# A-__LCP037BK32ET8-48V-SCH-V1_2-20230321.net
KiCad netlist of a schematic drawn in Altium Designer
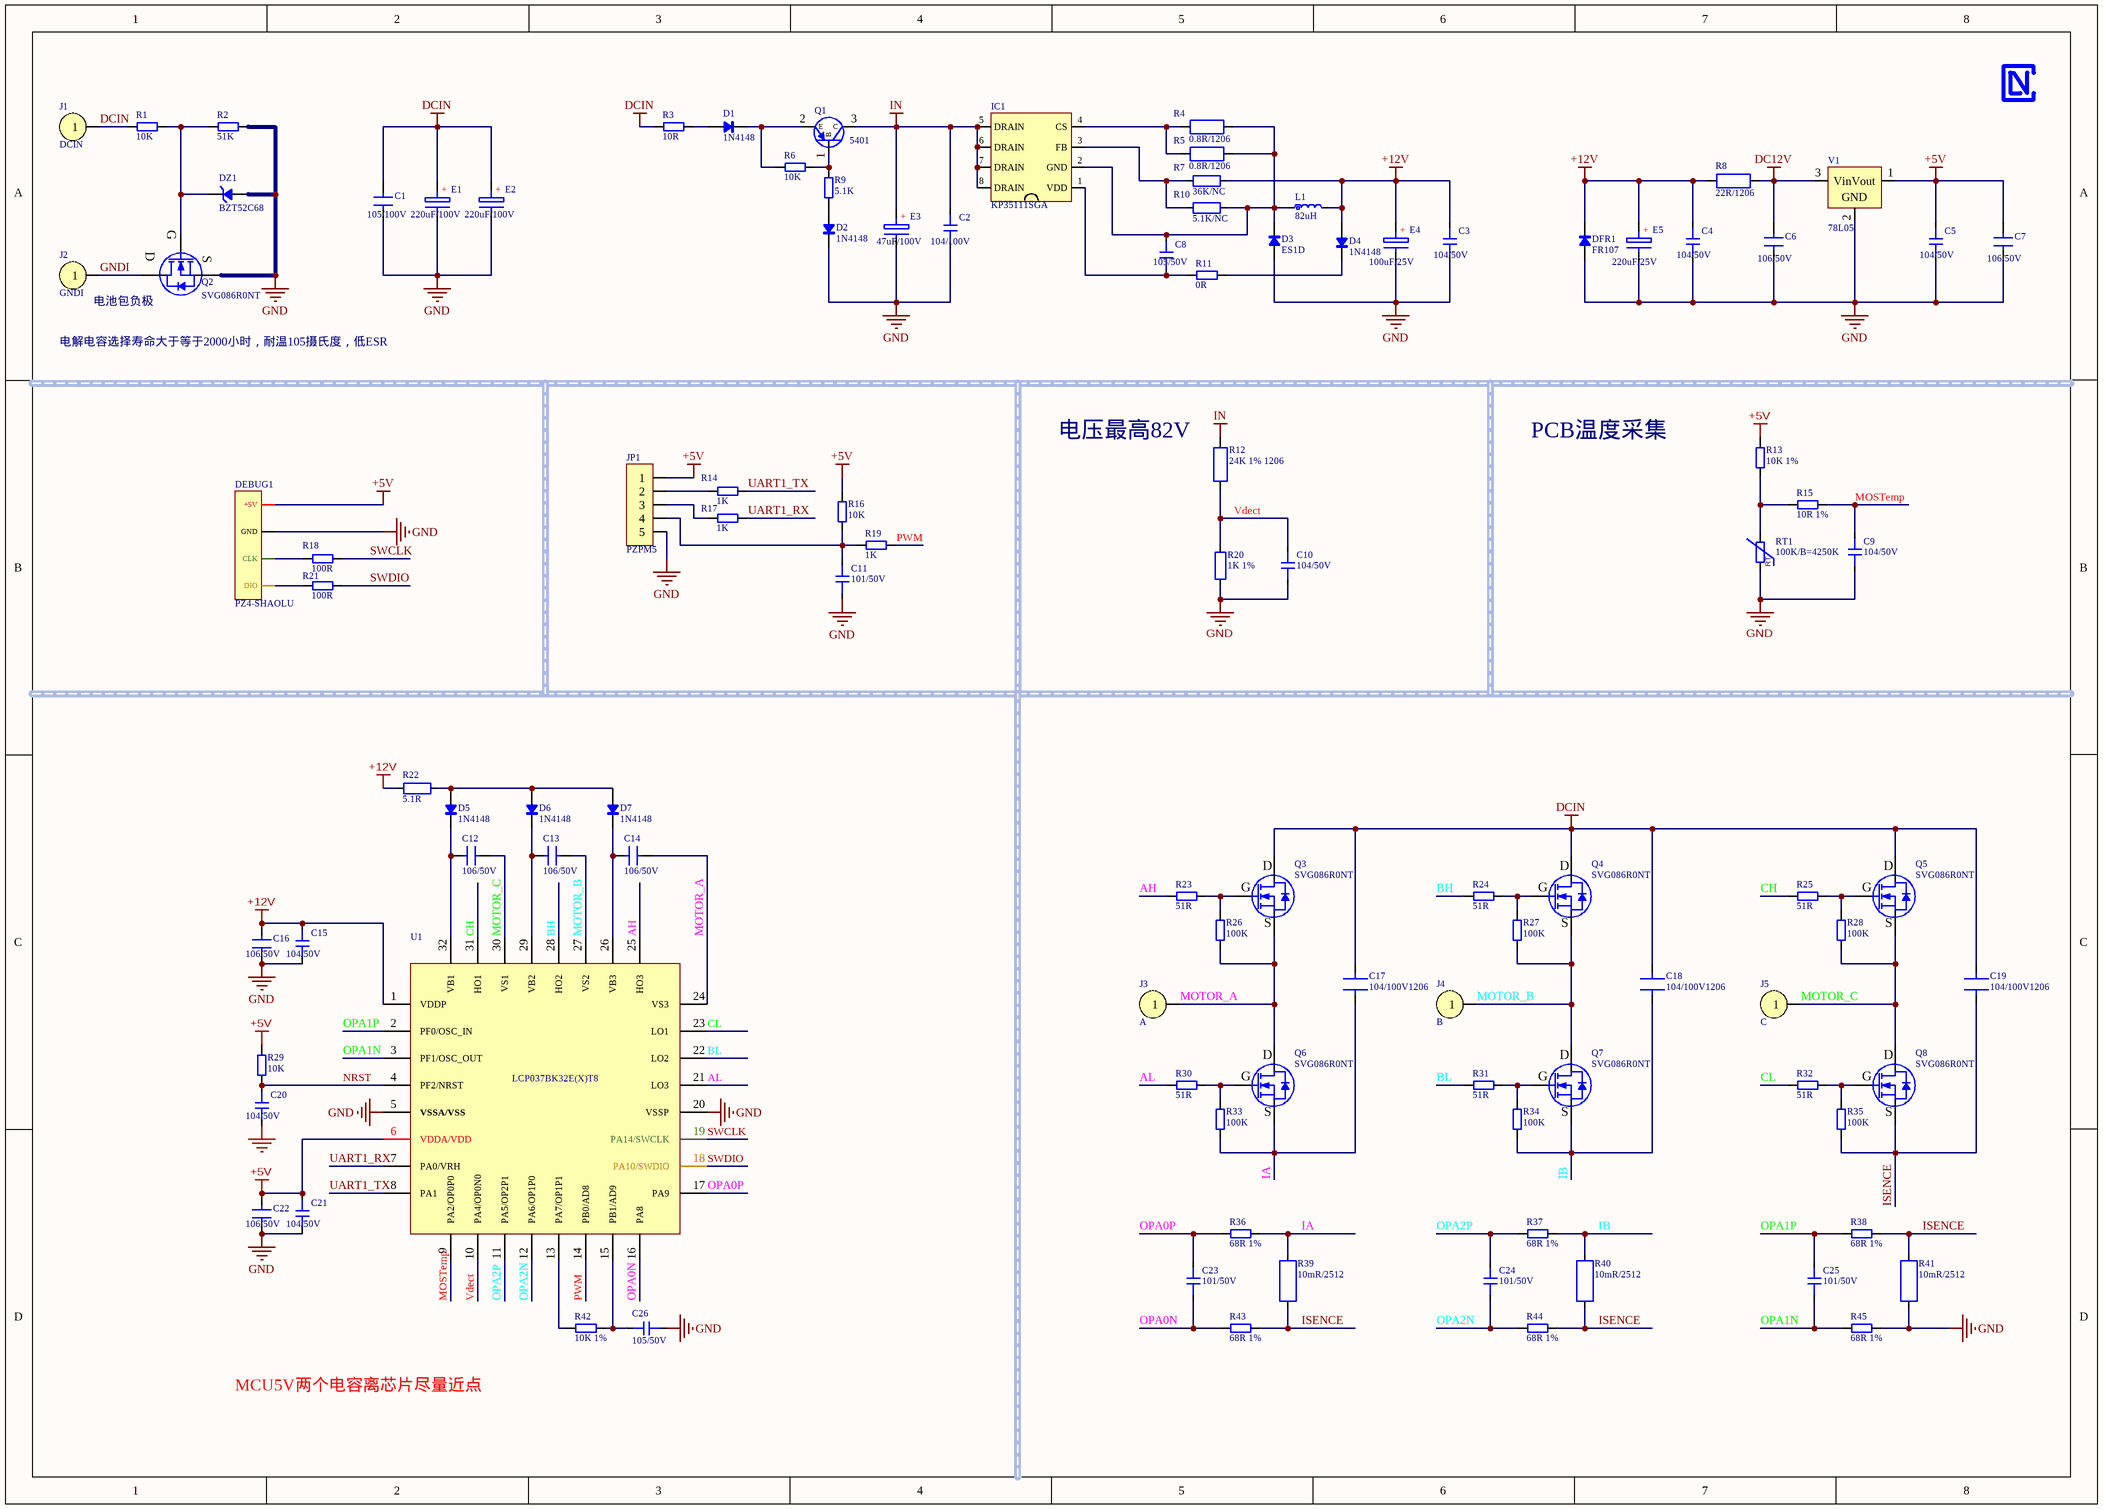
[diagram p0: A-水泵_LCP037BK32ET8-48V-SCH-V1.2-20230321.SchDoc]

(export (version "E")
  (design (tool "Eeschema 10.0.6"))
  (components
    (comp (ref "C1")
      (value "105/100V")
      (footprint "C0805")
      (description "0805")
      (libsource (lib "LNCHIP-KU-V1.2-20230210") (part "A_CAP_8"))
    )
    (comp (ref "C2")
      (value "104/100V")
      (footprint "C0603")
      (description "0603")
      (libsource (lib "LNCHIP-KU-V1.2-20230210") (part "A_CAP_6"))
    )
    (comp (ref "C3")
      (value "104/50V")
      (footprint "C0603")
      (description "0603")
      (libsource (lib "LNCHIP-KU-V1.2-20230210") (part "A_CAP_6"))
    )
    (comp (ref "C4")
      (value "104/50V")
      (footprint "C0603")
      (description "0603")
      (libsource (lib "LNCHIP-KU-V1.2-20230210") (part "A_CAP_6"))
    )
    (comp (ref "C5")
      (value "104/50V")
      (footprint "C0603")
      (description "0603")
      (libsource (lib "LNCHIP-KU-V1.2-20230210") (part "A_CAP_6"))
    )
    (comp (ref "C6")
      (value "106/50V")
      (footprint "C0805")
      (description "0805")
      (libsource (lib "LNCHIP-KU-V1.2-20230210") (part "A_CAP_8"))
    )
    (comp (ref "C7")
      (value "106/50V")
      (footprint "C0805")
      (description "0805")
      (libsource (lib "LNCHIP-KU-V1.2-20230210") (part "A_CAP_8"))
    )
    (comp (ref "C8")
      (value "105/50V")
      (footprint "C0603")
      (description "0603")
      (libsource (lib "LNCHIP-KU-V1.2-20230210") (part "A_CAP_6"))
    )
    (comp (ref "C9")
      (value "104/50V")
      (footprint "C0603")
      (description "0603")
      (libsource (lib "LNCHIP-KU-V1.2-20230210") (part "A_CAP_6"))
    )
    (comp (ref "C10")
      (value "104/50V")
      (footprint "C0603")
      (description "0603")
      (libsource (lib "LNCHIP-KU-V1.2-20230210") (part "A_CAP_6"))
    )
    (comp (ref "C11")
      (value "101/50V")
      (footprint "C0603")
      (description "0603")
      (libsource (lib "LNCHIP-KU-V1.2-20230210") (part "A_CAP_6"))
    )
    (comp (ref "C12")
      (value "106/50V")
      (footprint "C0805")
      (description "0805")
      (libsource (lib "LNCHIP-KU-V1.2-20230210") (part "A_CAP_8"))
    )
    (comp (ref "C13")
      (value "106/50V")
      (footprint "C0805")
      (description "0805")
      (libsource (lib "LNCHIP-KU-V1.2-20230210") (part "A_CAP_8"))
    )
    (comp (ref "C14")
      (value "106/50V")
      (footprint "C0805")
      (description "0805")
      (libsource (lib "LNCHIP-KU-V1.2-20230210") (part "A_CAP_8"))
    )
    (comp (ref "C15")
      (value "104/50V")
      (footprint "C0603")
      (description "0603")
      (libsource (lib "LNCHIP-KU-V1.2-20230210") (part "A_CAP_6"))
    )
    (comp (ref "C16")
      (value "106/50V")
      (footprint "C0805")
      (description "0805")
      (libsource (lib "LNCHIP-KU-V1.2-20230210") (part "A_CAP_8"))
    )
    (comp (ref "C17")
      (value "104/100V1206")
      (footprint "C1206")
      (description "1206/1808")
      (libsource (lib "LNCHIP-KU-V1.2-20230210") (part "A_CAP_12"))
    )
    (comp (ref "C18")
      (value "104/100V1206")
      (footprint "C1206")
      (description "1206/1808")
      (libsource (lib "LNCHIP-KU-V1.2-20230210") (part "A_CAP_12"))
    )
    (comp (ref "C19")
      (value "104/100V1206")
      (footprint "C1206")
      (description "1206/1808")
      (libsource (lib "LNCHIP-KU-V1.2-20230210") (part "A_CAP_12"))
    )
    (comp (ref "C20")
      (value "104/50V")
      (footprint "C0603")
      (description "0603")
      (libsource (lib "LNCHIP-KU-V1.2-20230210") (part "A_CAP_6"))
    )
    (comp (ref "C21")
      (value "104/50V")
      (footprint "C0603")
      (description "0603")
      (libsource (lib "LNCHIP-KU-V1.2-20230210") (part "A_CAP_6"))
    )
    (comp (ref "C22")
      (value "106/50V")
      (footprint "C0805")
      (description "0805")
      (libsource (lib "LNCHIP-KU-V1.2-20230210") (part "A_CAP_8"))
    )
    (comp (ref "C23")
      (value "101/50V")
      (footprint "C0603")
      (description "0603")
      (libsource (lib "LNCHIP-KU-V1.2-20230210") (part "A_CAP_6"))
    )
    (comp (ref "C24")
      (value "101/50V")
      (footprint "C0603")
      (description "0603")
      (libsource (lib "LNCHIP-KU-V1.2-20230210") (part "A_CAP_6"))
    )
    (comp (ref "C25")
      (value "101/50V")
      (footprint "C0603")
      (description "0603")
      (libsource (lib "LNCHIP-KU-V1.2-20230210") (part "A_CAP_6"))
    )
    (comp (ref "C26")
      (value "105/50V")
      (footprint "C0603")
      (description "0603")
      (libsource (lib "LNCHIP-KU-V1.2-20230210") (part "A_CAP_6"))
    )
    (comp (ref "D1")
      (value "1N4148")
      (footprint "SOD-123")
      (description "二极管/高效率/通用")
      (libsource (lib "LNCHIP-KU-V1.2-20230210") (part "DIO"))
    )
    (comp (ref "D2")
      (value "1N4148")
      (footprint "SOD-123")
      (description "二极管/高效率/通用")
      (libsource (lib "LNCHIP-KU-V1.2-20230210") (part "DIO"))
    )
    (comp (ref "D3")
      (value "ES1D")
      (footprint "SOD-123")
      (description "二极管/高效率/通用")
      (libsource (lib "LNCHIP-KU-V1.2-20230210") (part "DIO"))
    )
    (comp (ref "D4")
      (value "1N4148")
      (footprint "SOD-123")
      (description "二极管/高效率/通用")
      (libsource (lib "LNCHIP-KU-V1.2-20230210") (part "DIO"))
    )
    (comp (ref "D5")
      (value "1N4148")
      (footprint "SOD-123")
      (description "二极管/高效率/通用")
      (libsource (lib "LNCHIP-KU-V1.2-20230210") (part "DIO"))
    )
    (comp (ref "D6")
      (value "1N4148")
      (footprint "SOD-123")
      (description "二极管/高效率/通用")
      (libsource (lib "LNCHIP-KU-V1.2-20230210") (part "DIO"))
    )
    (comp (ref "D7")
      (value "1N4148")
      (footprint "SOD-123")
      (description "二极管/高效率/通用")
      (libsource (lib "LNCHIP-KU-V1.2-20230210") (part "DIO"))
    )
    (comp (ref "DEBUG1")
      (value "PZ4-SHAOLU")
      (footprint "PZ2.54-D-4P")
      (description "烧录口")
      (libsource (lib "LNCHIP-KU-V1.2-20230210") (part "PZ4-SHAOLU"))
    )
    (comp (ref "DFR1")
      (value "FR107")
      (footprint "SMA")
      (description "快/超快恢复二极管")
      (libsource (lib "LNCHIP-KU-V1.2-20230210") (part "DIO_FR(E)D"))
    )
    (comp (ref "DZ1")
      (value "BZT52C68")
      (footprint "SOD-123")
      (description "稳压管")
      (libsource (lib "LNCHIP-KU-V1.2-20230210") (part "DIO_ZENER"))
    )
    (comp (ref "E1")
      (value "220uF/100V")
      (footprint "CE-5.0-10")
      (description "直插电解电容")
      (libsource (lib "LNCHIP-KU-V1.2-20230210") (part "A_CAP_CE_DIP"))
    )
    (comp (ref "E2")
      (value "220uF/100V")
      (footprint "CE-5.0-10")
      (description "直插电解电容")
      (libsource (lib "LNCHIP-KU-V1.2-20230210") (part "A_CAP_CE_DIP"))
    )
    (comp (ref "E3")
      (value "47uF/100V")
      (footprint "CE-3.5-8")
      (description "直插电解电容")
      (libsource (lib "LNCHIP-KU-V1.2-20230210") (part "A_CAP_CE_DIP"))
    )
    (comp (ref "E4")
      (value "100uF/25V")
      (footprint "CE-2.5-5")
      (description "直插电解电容")
      (libsource (lib "LNCHIP-KU-V1.2-20230210") (part "A_CAP_CE_DIP"))
    )
    (comp (ref "E5")
      (value "220uF/25V")
      (footprint "CE-2.5-5")
      (description "直插电解电容")
      (libsource (lib "LNCHIP-KU-V1.2-20230210") (part "A_CAP_CE_DIP"))
    )
    (comp (ref "IC1")
      (value "KP35111SGA")
      (footprint "SOP-8_150_50")
      (description "功率电子开关/BUCK_DC-DC")
      (libsource (lib "LNCHIP-KU-V1.2-20230210") (part "IC_DY_KP35111"))
    )
    (comp (ref "J1")
      (value "DCIN")
      (footprint "HOLD-16AWG")
      (description "直插孔")
      (libsource (lib "LNCHIP-KU-V1.2-20230210") (part "CON_DIP"))
    )
    (comp (ref "J2")
      (value "GNDI")
      (footprint "HOLD-16AWG")
      (description "直插孔")
      (libsource (lib "LNCHIP-KU-V1.2-20230210") (part "CON_DIP"))
    )
    (comp (ref "J3")
      (value "A")
      (footprint "HOLD-16AWG")
      (description "直插孔")
      (libsource (lib "LNCHIP-KU-V1.2-20230210") (part "CON_DIP"))
    )
    (comp (ref "J4")
      (value "B")
      (footprint "HOLD-16AWG")
      (description "直插孔")
      (libsource (lib "LNCHIP-KU-V1.2-20230210") (part "CON_DIP"))
    )
    (comp (ref "J5")
      (value "C")
      (footprint "HOLD-16AWG")
      (description "直插孔")
      (libsource (lib "LNCHIP-KU-V1.2-20230210") (part "CON_DIP"))
    )
    (comp (ref "JP1")
      (value "PZPM5")
      (footprint "PZ2.54-D-5P")
      (description "排针排母")
      (libsource (lib "LNCHIP-KU-V1.2-20230210") (part "PZPM5"))
    )
    (comp (ref "L1")
      (value "82uH")
      (footprint "L-CDRH74")
      (description "贴片电感")
      (libsource (lib "LNCHIP-KU-V1.2-20230210") (part "INDUCTOR"))
    )
    (comp (ref "Q1")
      (value "5401")
      (footprint "SOT23-3")
      (description "PNP三极管")
      (libsource (lib "LNCHIP-KU-V1.2-20230210") (part "D_BJT_N"))
    )
    (comp (ref "Q2")
      (value "SVG086R0NT")
      (footprint "TO220")
      (description "N沟道")
      (libsource (lib "LNCHIP-KU-V1.2-20230210") (part "D_MOS_N-2D/"))
    )
    (comp (ref "Q3")
      (value "SVG086R0NT")
      (footprint "TO220")
      (description "N沟道")
      (libsource (lib "LNCHIP-KU-V1.2-20230210") (part "D_MOS_N-2D/"))
    )
    (comp (ref "Q4")
      (value "SVG086R0NT")
      (footprint "TO220")
      (description "N沟道")
      (libsource (lib "LNCHIP-KU-V1.2-20230210") (part "D_MOS_N-2D/"))
    )
    (comp (ref "Q5")
      (value "SVG086R0NT")
      (footprint "TO220")
      (description "N沟道")
      (libsource (lib "LNCHIP-KU-V1.2-20230210") (part "D_MOS_N-2D/"))
    )
    (comp (ref "Q6")
      (value "SVG086R0NT")
      (footprint "TO220")
      (description "N沟道")
      (libsource (lib "LNCHIP-KU-V1.2-20230210") (part "D_MOS_N-2D/"))
    )
    (comp (ref "Q7")
      (value "SVG086R0NT")
      (footprint "TO220")
      (description "N沟道")
      (libsource (lib "LNCHIP-KU-V1.2-20230210") (part "D_MOS_N-2D/"))
    )
    (comp (ref "Q8")
      (value "SVG086R0NT")
      (footprint "TO220")
      (description "N沟道")
      (libsource (lib "LNCHIP-KU-V1.2-20230210") (part "D_MOS_N-2D/"))
    )
    (comp (ref "R1")
      (value "10K")
      (footprint "R0603")
      (description "0603")
      (libsource (lib "LNCHIP-KU-V1.2-20230210") (part "A_RES_6"))
    )
    (comp (ref "R2")
      (value "51K")
      (footprint "R0603")
      (description "0603")
      (libsource (lib "LNCHIP-KU-V1.2-20230210") (part "A_RES_6"))
    )
    (comp (ref "R3")
      (value "10R")
      (footprint "R0603")
      (description "0603")
      (libsource (lib "LNCHIP-KU-V1.2-20230210") (part "A_RES_6"))
    )
    (comp (ref "R4")
      (value "0.8R/1206")
      (footprint "R1206")
      (description "1206")
      (libsource (lib "LNCHIP-KU-V1.2-20230210") (part "A_RES_12"))
    )
    (comp (ref "R5")
      (value "0.8R/1206")
      (footprint "R1206")
      (description "1206")
      (libsource (lib "LNCHIP-KU-V1.2-20230210") (part "A_RES_12"))
    )
    (comp (ref "R6")
      (value "10K")
      (footprint "R0603")
      (description "0603")
      (libsource (lib "LNCHIP-KU-V1.2-20230210") (part "A_RES_6"))
    )
    (comp (ref "R7")
      (value "36K/NC")
      (footprint "R0805")
      (description "0805")
      (libsource (lib "LNCHIP-KU-V1.2-20230210") (part "A_RES_8"))
    )
    (comp (ref "R8")
      (value "22R/1206")
      (footprint "R1206")
      (description "1206")
      (libsource (lib "LNCHIP-KU-V1.2-20230210") (part "A_RES_12"))
    )
    (comp (ref "R9")
      (value "5.1K")
      (footprint "R0603")
      (description "0603")
      (libsource (lib "LNCHIP-KU-V1.2-20230210") (part "A_RES_6"))
    )
    (comp (ref "R10")
      (value "5.1K/NC")
      (footprint "R0805")
      (description "0805")
      (libsource (lib "LNCHIP-KU-V1.2-20230210") (part "A_RES_8"))
    )
    (comp (ref "R11")
      (value "0R")
      (footprint "R0603")
      (description "0603")
      (libsource (lib "LNCHIP-KU-V1.2-20230210") (part "A_RES_6"))
    )
    (comp (ref "R12")
      (value "24K 1% 1206")
      (footprint "R1206")
      (description "1206")
      (libsource (lib "LNCHIP-KU-V1.2-20230210") (part "A_RES_12"))
    )
    (comp (ref "R13")
      (value "10K 1%")
      (footprint "R0603")
      (description "0603")
      (libsource (lib "LNCHIP-KU-V1.2-20230210") (part "A_RES_6"))
    )
    (comp (ref "R14")
      (value "1K")
      (footprint "R0603")
      (description "0603")
      (libsource (lib "LNCHIP-KU-V1.2-20230210") (part "A_RES_6"))
    )
    (comp (ref "R15")
      (value "10R 1%")
      (footprint "R0603")
      (description "0603")
      (libsource (lib "LNCHIP-KU-V1.2-20230210") (part "A_RES_6"))
    )
    (comp (ref "R16")
      (value "10K")
      (footprint "R0603")
      (description "0603")
      (libsource (lib "LNCHIP-KU-V1.2-20230210") (part "A_RES_6"))
    )
    (comp (ref "R17")
      (value "1K")
      (footprint "R0603")
      (description "0603")
      (libsource (lib "LNCHIP-KU-V1.2-20230210") (part "A_RES_6"))
    )
    (comp (ref "R18")
      (value "100R")
      (footprint "R0603")
      (description "0603")
      (libsource (lib "LNCHIP-KU-V1.2-20230210") (part "A_RES_6"))
    )
    (comp (ref "R19")
      (value "1K")
      (footprint "R0603")
      (description "0603")
      (libsource (lib "LNCHIP-KU-V1.2-20230210") (part "A_RES_6"))
    )
    (comp (ref "R20")
      (value "1K 1%")
      (footprint "R0805")
      (description "0805")
      (libsource (lib "LNCHIP-KU-V1.2-20230210") (part "A_RES_8"))
    )
    (comp (ref "R21")
      (value "100R")
      (footprint "R0603")
      (description "0603")
      (libsource (lib "LNCHIP-KU-V1.2-20230210") (part "A_RES_6"))
    )
    (comp (ref "R22")
      (value "5.1R")
      (footprint "R0805")
      (description "0805")
      (libsource (lib "LNCHIP-KU-V1.2-20230210") (part "A_RES_8"))
    )
    (comp (ref "R23")
      (value "51R")
      (footprint "R0603")
      (description "0603")
      (libsource (lib "LNCHIP-KU-V1.2-20230210") (part "A_RES_6"))
    )
    (comp (ref "R24")
      (value "51R")
      (footprint "R0603")
      (description "0603")
      (libsource (lib "LNCHIP-KU-V1.2-20230210") (part "A_RES_6"))
    )
    (comp (ref "R25")
      (value "51R")
      (footprint "R0603")
      (description "0603")
      (libsource (lib "LNCHIP-KU-V1.2-20230210") (part "A_RES_6"))
    )
    (comp (ref "R26")
      (value "100K")
      (footprint "R0603")
      (description "0603")
      (libsource (lib "LNCHIP-KU-V1.2-20230210") (part "A_RES_6"))
    )
    (comp (ref "R27")
      (value "100K")
      (footprint "R0603")
      (description "0603")
      (libsource (lib "LNCHIP-KU-V1.2-20230210") (part "A_RES_6"))
    )
    (comp (ref "R28")
      (value "100K")
      (footprint "R0603")
      (description "0603")
      (libsource (lib "LNCHIP-KU-V1.2-20230210") (part "A_RES_6"))
    )
    (comp (ref "R29")
      (value "10K")
      (footprint "R0603")
      (description "0603")
      (libsource (lib "LNCHIP-KU-V1.2-20230210") (part "A_RES_6"))
    )
    (comp (ref "R30")
      (value "51R")
      (footprint "R0603")
      (description "0603")
      (libsource (lib "LNCHIP-KU-V1.2-20230210") (part "A_RES_6"))
    )
    (comp (ref "R31")
      (value "51R")
      (footprint "R0603")
      (description "0603")
      (libsource (lib "LNCHIP-KU-V1.2-20230210") (part "A_RES_6"))
    )
    (comp (ref "R32")
      (value "51R")
      (footprint "R0603")
      (description "0603")
      (libsource (lib "LNCHIP-KU-V1.2-20230210") (part "A_RES_6"))
    )
    (comp (ref "R33")
      (value "100K")
      (footprint "R0603")
      (description "0603")
      (libsource (lib "LNCHIP-KU-V1.2-20230210") (part "A_RES_6"))
    )
    (comp (ref "R34")
      (value "100K")
      (footprint "R0603")
      (description "0603")
      (libsource (lib "LNCHIP-KU-V1.2-20230210") (part "A_RES_6"))
    )
    (comp (ref "R35")
      (value "100K")
      (footprint "R0603")
      (description "0603")
      (libsource (lib "LNCHIP-KU-V1.2-20230210") (part "A_RES_6"))
    )
    (comp (ref "R36")
      (value "68R 1%")
      (footprint "R0603")
      (description "0603")
      (libsource (lib "LNCHIP-KU-V1.2-20230210") (part "A_RES_6"))
    )
    (comp (ref "R37")
      (value "68R 1%")
      (footprint "R0603")
      (description "0603")
      (libsource (lib "LNCHIP-KU-V1.2-20230210") (part "A_RES_6"))
    )
    (comp (ref "R38")
      (value "68R 1%")
      (footprint "R0603")
      (description "0603")
      (libsource (lib "LNCHIP-KU-V1.2-20230210") (part "A_RES_6"))
    )
    (comp (ref "R39")
      (value "10mR/2512")
      (footprint "R2512")
      (description "2512")
      (libsource (lib "LNCHIP-KU-V1.2-20230210") (part "A_RES_25"))
    )
    (comp (ref "R40")
      (value "10mR/2512")
      (footprint "R2512")
      (description "2512")
      (libsource (lib "LNCHIP-KU-V1.2-20230210") (part "A_RES_25"))
    )
    (comp (ref "R41")
      (value "10mR/2512")
      (footprint "R2512")
      (description "2512")
      (libsource (lib "LNCHIP-KU-V1.2-20230210") (part "A_RES_25"))
    )
    (comp (ref "R42")
      (value "10K 1%")
      (footprint "R0603")
      (description "0603")
      (libsource (lib "LNCHIP-KU-V1.2-20230210") (part "A_RES_6"))
    )
    (comp (ref "R43")
      (value "68R 1%")
      (footprint "R0603")
      (description "0603")
      (libsource (lib "LNCHIP-KU-V1.2-20230210") (part "A_RES_6"))
    )
    (comp (ref "R44")
      (value "68R 1%")
      (footprint "R0603")
      (description "0603")
      (libsource (lib "LNCHIP-KU-V1.2-20230210") (part "A_RES_6"))
    )
    (comp (ref "R45")
      (value "68R 1%")
      (footprint "R0603")
      (description "0603")
      (libsource (lib "LNCHIP-KU-V1.2-20230210") (part "A_RES_6"))
    )
    (comp (ref "RT1")
      (value "100K/B=4250K")
      (footprint "NTC-S-0603")
      (description "热敏电阻")
      (libsource (lib "LNCHIP-KU-V1.2-20230210") (part "A_RES_NTC_SMD"))
    )
    (comp (ref "U1")
      (value "LCP037BK32E(X)T8")
      (footprint "LNCP-LQFP32-7X7-0.8")
      (description "037合封BK32E(X)T8")
      (libsource (lib "LNCHIP-KU-V1.2-20230210") (part "MCU_电机_32位_037_B1"))
    )
    (comp (ref "V1")
      (value "78L05")
      (footprint "SOT89")
      (description "BUCK_DC-DC")
      (libsource (lib "LNCHIP-KU-V1.2-20230210") (part "LDO_2D/"))
    )
  )
  (nets
    (net (code "1") (name "+5V") (class "Default")
      (node (ref "C21") (pin "1") (pinfunction "1_1") (pintype "passive"))
      (node (ref "C22") (pin "1") (pinfunction "1_1") (pintype "passive"))
      (node (ref "C5") (pin "1") (pinfunction "1_1") (pintype "passive"))
      (node (ref "C7") (pin "1") (pinfunction "1_1") (pintype "passive"))
      (node (ref "DEBUG1") (pin "1") (pinfunction "+5V_1") (pintype "passive"))
      (node (ref "JP1") (pin "1") (pinfunction "1_1") (pintype "passive"))
      (node (ref "R13") (pin "2") (pinfunction "2_2") (pintype "passive"))
      (node (ref "R16") (pin "2") (pinfunction "2_2") (pintype "passive"))
      (node (ref "R29") (pin "2") (pinfunction "2_2") (pintype "passive"))
      (node (ref "U1") (pin "6") (pinfunction "VDDA/VDD_6") (pintype "passive"))
      (node (ref "V1") (pin "1") (pinfunction "Vout_1") (pintype "passive"))
    )
    (net (code "2") (name "+12V") (class "Default")
      (node (ref "C15") (pin "1") (pinfunction "1_1") (pintype "passive"))
      (node (ref "C16") (pin "1") (pinfunction "1_1") (pintype "passive"))
      (node (ref "C3") (pin "1") (pinfunction "1_1") (pintype "passive"))
      (node (ref "C4") (pin "1") (pinfunction "1_1") (pintype "passive"))
      (node (ref "D4") (pin "1") (pinfunction "A_1") (pintype "passive"))
      (node (ref "DFR1") (pin "2") (pinfunction "K_2") (pintype "passive"))
      (node (ref "E4") (pin "1") (pinfunction "1_1") (pintype "passive"))
      (node (ref "E5") (pin "1") (pinfunction "1_1") (pintype "passive"))
      (node (ref "L1") (pin "2") (pinfunction "2_2") (pintype "passive"))
      (node (ref "R22") (pin "1") (pinfunction "1_1") (pintype "passive"))
      (node (ref "R7") (pin "2") (pinfunction "2_2") (pintype "passive"))
      (node (ref "R8") (pin "1") (pinfunction "1_1") (pintype "passive"))
      (node (ref "U1") (pin "1") (pinfunction "VDDP_1") (pintype "passive"))
    )
    (net (code "3") (name "/AH") (class "Default")
      (node (ref "R23") (pin "1") (pinfunction "1_1") (pintype "passive"))
      (node (ref "U1") (pin "25") (pinfunction "HO3_25") (pintype "passive"))
    )
    (net (code "4") (name "/AL") (class "Default")
      (node (ref "R30") (pin "1") (pinfunction "1_1") (pintype "passive"))
      (node (ref "U1") (pin "21") (pinfunction "LO3_21") (pintype "passive"))
    )
    (net (code "5") (name "/BH") (class "Default")
      (node (ref "R24") (pin "1") (pinfunction "1_1") (pintype "passive"))
      (node (ref "U1") (pin "28") (pinfunction "HO2_28") (pintype "passive"))
    )
    (net (code "6") (name "/BL") (class "Default")
      (node (ref "R31") (pin "1") (pinfunction "1_1") (pintype "passive"))
      (node (ref "U1") (pin "22") (pinfunction "LO2_22") (pintype "passive"))
    )
    (net (code "7") (name "/CH") (class "Default")
      (node (ref "R25") (pin "1") (pinfunction "1_1") (pintype "passive"))
      (node (ref "U1") (pin "31") (pinfunction "HO1_31") (pintype "passive"))
    )
    (net (code "8") (name "/CL") (class "Default")
      (node (ref "R32") (pin "1") (pinfunction "1_1") (pintype "passive"))
      (node (ref "U1") (pin "23") (pinfunction "LO1_23") (pintype "passive"))
    )
    (net (code "9") (name "/GNDI") (class "Default")
      (node (ref "J2") (pin "1") (pinfunction "1_1") (pintype "passive"))
      (node (ref "Q2") (pin "2") (pinfunction "D_2") (pintype "passive"))
    )
    (net (code "10") (name "/IA") (class "Default")
      (node (ref "C17") (pin "2") (pinfunction "2_2") (pintype "passive"))
      (node (ref "Q6") (pin "3") (pinfunction "S_3") (pintype "passive"))
      (node (ref "R33") (pin "1") (pinfunction "1_1") (pintype "passive"))
      (node (ref "R36") (pin "2") (pinfunction "2_2") (pintype "passive"))
      (node (ref "R39") (pin "2") (pinfunction "2_2") (pintype "passive"))
    )
    (net (code "11") (name "/IB") (class "Default")
      (node (ref "C18") (pin "2") (pinfunction "2_2") (pintype "passive"))
      (node (ref "Q7") (pin "3") (pinfunction "S_3") (pintype "passive"))
      (node (ref "R34") (pin "1") (pinfunction "1_1") (pintype "passive"))
      (node (ref "R37") (pin "2") (pinfunction "2_2") (pintype "passive"))
      (node (ref "R40") (pin "2") (pinfunction "2_2") (pintype "passive"))
    )
    (net (code "12") (name "/ISENCE") (class "Default")
      (node (ref "C19") (pin "2") (pinfunction "2_2") (pintype "passive"))
      (node (ref "Q8") (pin "3") (pinfunction "S_3") (pintype "passive"))
      (node (ref "R35") (pin "1") (pinfunction "1_1") (pintype "passive"))
      (node (ref "R38") (pin "2") (pinfunction "2_2") (pintype "passive"))
      (node (ref "R39") (pin "1") (pinfunction "1_1") (pintype "passive"))
      (node (ref "R40") (pin "1") (pinfunction "1_1") (pintype "passive"))
      (node (ref "R41") (pin "2") (pinfunction "2_2") (pintype "passive"))
      (node (ref "R43") (pin "2") (pinfunction "2_2") (pintype "passive"))
      (node (ref "R44") (pin "2") (pinfunction "2_2") (pintype "passive"))
    )
    (net (code "13") (name "/MOSTemp") (class "Default")
      (node (ref "C9") (pin "1") (pinfunction "1_1") (pintype "passive"))
      (node (ref "R15") (pin "1") (pinfunction "1_1") (pintype "passive"))
      (node (ref "U1") (pin "9") (pinfunction "PA2/OP0P0_9") (pintype "passive"))
    )
    (net (code "14") (name "/MOTOR_A") (class "Default")
      (node (ref "C14") (pin "2") (pinfunction "2_2") (pintype "passive"))
      (node (ref "J3") (pin "1") (pinfunction "1_1") (pintype "passive"))
      (node (ref "Q3") (pin "3") (pinfunction "S_3") (pintype "passive"))
      (node (ref "Q6") (pin "2") (pinfunction "D_2") (pintype "passive"))
      (node (ref "R26") (pin "1") (pinfunction "1_1") (pintype "passive"))
      (node (ref "U1") (pin "24") (pinfunction "VS3_24") (pintype "passive"))
    )
    (net (code "15") (name "/MOTOR_B") (class "Default")
      (node (ref "C13") (pin "2") (pinfunction "2_2") (pintype "passive"))
      (node (ref "J4") (pin "1") (pinfunction "1_1") (pintype "passive"))
      (node (ref "Q4") (pin "3") (pinfunction "S_3") (pintype "passive"))
      (node (ref "Q7") (pin "2") (pinfunction "D_2") (pintype "passive"))
      (node (ref "R27") (pin "1") (pinfunction "1_1") (pintype "passive"))
      (node (ref "U1") (pin "27") (pinfunction "VS2_27") (pintype "passive"))
    )
    (net (code "16") (name "/MOTOR_C") (class "Default")
      (node (ref "C12") (pin "2") (pinfunction "2_2") (pintype "passive"))
      (node (ref "J5") (pin "1") (pinfunction "1_1") (pintype "passive"))
      (node (ref "Q5") (pin "3") (pinfunction "S_3") (pintype "passive"))
      (node (ref "Q8") (pin "2") (pinfunction "D_2") (pintype "passive"))
      (node (ref "R28") (pin "1") (pinfunction "1_1") (pintype "passive"))
      (node (ref "U1") (pin "30") (pinfunction "VS1_30") (pintype "passive"))
    )
    (net (code "17") (name "/NRST") (class "Default")
      (node (ref "C20") (pin "1") (pinfunction "1_1") (pintype "passive"))
      (node (ref "R29") (pin "1") (pinfunction "1_1") (pintype "passive"))
      (node (ref "U1") (pin "4") (pinfunction "PF2/NRST_4") (pintype "passive"))
    )
    (net (code "18") (name "/OPA0N") (class "Default")
      (node (ref "C23") (pin "2") (pinfunction "2_2") (pintype "passive"))
      (node (ref "R43") (pin "1") (pinfunction "1_1") (pintype "passive"))
      (node (ref "U1") (pin "16") (pinfunction "PA8_16") (pintype "passive"))
    )
    (net (code "19") (name "/OPA0P") (class "Default")
      (node (ref "C23") (pin "1") (pinfunction "1_1") (pintype "passive"))
      (node (ref "R36") (pin "1") (pinfunction "1_1") (pintype "passive"))
      (node (ref "U1") (pin "17") (pinfunction "PA9_17") (pintype "passive"))
    )
    (net (code "20") (name "/OPA1N") (class "Default")
      (node (ref "C25") (pin "2") (pinfunction "2_2") (pintype "passive"))
      (node (ref "R45") (pin "1") (pinfunction "1_1") (pintype "passive"))
      (node (ref "U1") (pin "3") (pinfunction "PF1/OSC_OUT_3") (pintype "passive"))
    )
    (net (code "21") (name "/OPA1P") (class "Default")
      (node (ref "C25") (pin "1") (pinfunction "1_1") (pintype "passive"))
      (node (ref "R38") (pin "1") (pinfunction "1_1") (pintype "passive"))
      (node (ref "U1") (pin "2") (pinfunction "PF0/OSC_IN_2") (pintype "passive"))
    )
    (net (code "22") (name "/OPA2N") (class "Default")
      (node (ref "C24") (pin "2") (pinfunction "2_2") (pintype "passive"))
      (node (ref "R44") (pin "1") (pinfunction "1_1") (pintype "passive"))
      (node (ref "U1") (pin "12") (pinfunction "PA6/OP1P0_12") (pintype "passive"))
    )
    (net (code "23") (name "/OPA2P") (class "Default")
      (node (ref "C24") (pin "1") (pinfunction "1_1") (pintype "passive"))
      (node (ref "R37") (pin "1") (pinfunction "1_1") (pintype "passive"))
      (node (ref "U1") (pin "11") (pinfunction "PA5/OP2P1_11") (pintype "passive"))
    )
    (net (code "24") (name "/PWM") (class "Default")
      (node (ref "R19") (pin "2") (pinfunction "2_2") (pintype "passive"))
      (node (ref "U1") (pin "14") (pinfunction "PB0/AD8_14") (pintype "passive"))
    )
    (net (code "25") (name "/SWCLK") (class "Default")
      (node (ref "R18") (pin "2") (pinfunction "2_2") (pintype "passive"))
      (node (ref "U1") (pin "19") (pinfunction "PA14/SWCLK_19") (pintype "passive"))
    )
    (net (code "26") (name "/SWDIO") (class "Default")
      (node (ref "R21") (pin "2") (pinfunction "2_2") (pintype "passive"))
      (node (ref "U1") (pin "18") (pinfunction "PA10/SWDIO_18") (pintype "passive"))
    )
    (net (code "27") (name "/UART1_RX") (class "Default")
      (node (ref "R17") (pin "2") (pinfunction "2_2") (pintype "passive"))
      (node (ref "U1") (pin "7") (pinfunction "PA0/VRH_7") (pintype "passive"))
    )
    (net (code "28") (name "/UART1_TX") (class "Default")
      (node (ref "R14") (pin "2") (pinfunction "2_2") (pintype "passive"))
      (node (ref "U1") (pin "8") (pinfunction "PA1_8") (pintype "passive"))
    )
    (net (code "29") (name "/Vdect") (class "Default")
      (node (ref "C10") (pin "1") (pinfunction "1_1") (pintype "passive"))
      (node (ref "R12") (pin "1") (pinfunction "1_1") (pintype "passive"))
      (node (ref "R20") (pin "2") (pinfunction "2_2") (pintype "passive"))
      (node (ref "U1") (pin "10") (pinfunction "PA4/OP0N0_10") (pintype "passive"))
    )
    (net (code "30") (name "DC12V") (class "Default")
      (node (ref "C6") (pin "1") (pinfunction "1_1") (pintype "passive"))
      (node (ref "R8") (pin "2") (pinfunction "2_2") (pintype "passive"))
      (node (ref "V1") (pin "3") (pinfunction "Vin_3") (pintype "passive"))
    )
    (net (code "31") (name "DCIN") (class "Default")
      (node (ref "C1") (pin "1") (pinfunction "1_1") (pintype "passive"))
      (node (ref "C17") (pin "1") (pinfunction "1_1") (pintype "passive"))
      (node (ref "C18") (pin "1") (pinfunction "1_1") (pintype "passive"))
      (node (ref "C19") (pin "1") (pinfunction "1_1") (pintype "passive"))
      (node (ref "E1") (pin "1") (pinfunction "1_1") (pintype "passive"))
      (node (ref "E2") (pin "1") (pinfunction "1_1") (pintype "passive"))
      (node (ref "J1") (pin "1") (pinfunction "1_1") (pintype "passive"))
      (node (ref "Q3") (pin "2") (pinfunction "D_2") (pintype "passive"))
      (node (ref "Q4") (pin "2") (pinfunction "D_2") (pintype "passive"))
      (node (ref "Q5") (pin "2") (pinfunction "D_2") (pintype "passive"))
      (node (ref "R1") (pin "1") (pinfunction "1_1") (pintype "passive"))
      (node (ref "R3") (pin "1") (pinfunction "1_1") (pintype "passive"))
    )
    (net (code "32") (name "GND") (class "Default")
      (node (ref "C1") (pin "2") (pinfunction "2_2") (pintype "passive"))
      (node (ref "C10") (pin "2") (pinfunction "2_2") (pintype "passive"))
      (node (ref "C11") (pin "2") (pinfunction "2_2") (pintype "passive"))
      (node (ref "C15") (pin "2") (pinfunction "2_2") (pintype "passive"))
      (node (ref "C16") (pin "2") (pinfunction "2_2") (pintype "passive"))
      (node (ref "C2") (pin "2") (pinfunction "2_2") (pintype "passive"))
      (node (ref "C20") (pin "2") (pinfunction "2_2") (pintype "passive"))
      (node (ref "C21") (pin "2") (pinfunction "2_2") (pintype "passive"))
      (node (ref "C22") (pin "2") (pinfunction "2_2") (pintype "passive"))
      (node (ref "C26") (pin "2") (pinfunction "2_2") (pintype "passive"))
      (node (ref "C3") (pin "2") (pinfunction "2_2") (pintype "passive"))
      (node (ref "C4") (pin "2") (pinfunction "2_2") (pintype "passive"))
      (node (ref "C5") (pin "2") (pinfunction "2_2") (pintype "passive"))
      (node (ref "C6") (pin "2") (pinfunction "2_2") (pintype "passive"))
      (node (ref "C7") (pin "2") (pinfunction "2_2") (pintype "passive"))
      (node (ref "C9") (pin "2") (pinfunction "2_2") (pintype "passive"))
      (node (ref "D2") (pin "2") (pinfunction "K_2") (pintype "passive"))
      (node (ref "D3") (pin "1") (pinfunction "A_1") (pintype "passive"))
      (node (ref "DEBUG1") (pin "2") (pinfunction "GND_2") (pintype "passive"))
      (node (ref "DFR1") (pin "1") (pinfunction "A_1") (pintype "passive"))
      (node (ref "DZ1") (pin "1") (pinfunction "A_1") (pintype "passive"))
      (node (ref "E1") (pin "2") (pinfunction "2_2") (pintype "passive"))
      (node (ref "E2") (pin "2") (pinfunction "2_2") (pintype "passive"))
      (node (ref "E3") (pin "2") (pinfunction "2_2") (pintype "passive"))
      (node (ref "E4") (pin "2") (pinfunction "2_2") (pintype "passive"))
      (node (ref "E5") (pin "2") (pinfunction "2_2") (pintype "passive"))
      (node (ref "JP1") (pin "5") (pinfunction "5_5") (pintype "passive"))
      (node (ref "Q2") (pin "3") (pinfunction "S_3") (pintype "passive"))
      (node (ref "R2") (pin "2") (pinfunction "2_2") (pintype "passive"))
      (node (ref "R20") (pin "1") (pinfunction "1_1") (pintype "passive"))
      (node (ref "R41") (pin "1") (pinfunction "1_1") (pintype "passive"))
      (node (ref "R45") (pin "2") (pinfunction "2_2") (pintype "passive"))
      (node (ref "RT1") (pin "1") (pinfunction "1_1") (pintype "passive"))
      (node (ref "U1") (pin "20") (pinfunction "VSSP_20") (pintype "passive"))
      (node (ref "U1") (pin "5") (pinfunction "VSSA/VSS_5") (pintype "passive"))
      (node (ref "V1") (pin "2") (pinfunction "GND_2") (pintype "passive"))
    )
    (net (code "33") (name "IN") (class "Default")
      (node (ref "C2") (pin "1") (pinfunction "1_1") (pintype "passive"))
      (node (ref "E3") (pin "1") (pinfunction "1_1") (pintype "passive"))
      (node (ref "IC1") (pin "5") (pinfunction "DRAIN_5") (pintype "passive"))
      (node (ref "IC1") (pin "6") (pinfunction "DRAIN_6") (pintype "passive"))
      (node (ref "IC1") (pin "7") (pinfunction "DRAIN_7") (pintype "passive"))
      (node (ref "IC1") (pin "8") (pinfunction "DRAIN_8") (pintype "passive"))
      (node (ref "Q1") (pin "3") (pinfunction "C_3") (pintype "passive"))
      (node (ref "R12") (pin "2") (pinfunction "2_2") (pintype "passive"))
    )
    (net (code "34") (name "Net-(C11-Pad1)") (class "Default")
      (node (ref "C11") (pin "1") (pinfunction "1_1") (pintype "passive"))
      (node (ref "JP1") (pin "4") (pinfunction "4_4") (pintype "passive"))
      (node (ref "R16") (pin "1") (pinfunction "1_1") (pintype "passive"))
      (node (ref "R19") (pin "1") (pinfunction "1_1") (pintype "passive"))
    )
    (net (code "35") (name "Net-(D1-A)") (class "Default")
      (node (ref "D1") (pin "1") (pinfunction "A_1") (pintype "passive"))
      (node (ref "R3") (pin "2") (pinfunction "2_2") (pintype "passive"))
    )
    (net (code "36") (name "Net-(D1-K)") (class "Default")
      (node (ref "D1") (pin "2") (pinfunction "K_2") (pintype "passive"))
      (node (ref "Q1") (pin "2") (pinfunction "E_2") (pintype "passive"))
      (node (ref "R6") (pin "1") (pinfunction "1_1") (pintype "passive"))
    )
    (net (code "37") (name "Net-(D2-A)") (class "Default")
      (node (ref "D2") (pin "1") (pinfunction "A_1") (pintype "passive"))
      (node (ref "R9") (pin "1") (pinfunction "1_1") (pintype "passive"))
    )
    (net (code "38") (name "Net-(D3-K)") (class "Default")
      (node (ref "C8") (pin "1") (pinfunction "1_1") (pintype "passive"))
      (node (ref "D3") (pin "2") (pinfunction "K_2") (pintype "passive"))
      (node (ref "IC1") (pin "2") (pinfunction "GND_2") (pintype "passive"))
      (node (ref "L1") (pin "1") (pinfunction "1_1") (pintype "passive"))
      (node (ref "R10") (pin "2") (pinfunction "2_2") (pintype "passive"))
      (node (ref "R4") (pin "2") (pinfunction "2_2") (pintype "passive"))
      (node (ref "R5") (pin "2") (pinfunction "2_2") (pintype "passive"))
    )
    (net (code "39") (name "Net-(D4-K)") (class "Default")
      (node (ref "D4") (pin "2") (pinfunction "K_2") (pintype "passive"))
      (node (ref "R11") (pin "1") (pinfunction "1_1") (pintype "passive"))
    )
    (net (code "40") (name "Net-(D5-A)") (class "Default")
      (node (ref "D5") (pin "1") (pinfunction "A_1") (pintype "passive"))
      (node (ref "D6") (pin "1") (pinfunction "A_1") (pintype "passive"))
      (node (ref "D7") (pin "1") (pinfunction "A_1") (pintype "passive"))
      (node (ref "R22") (pin "2") (pinfunction "2_2") (pintype "passive"))
    )
    (net (code "41") (name "Net-(D5-K)") (class "Default")
      (node (ref "C12") (pin "1") (pinfunction "1_1") (pintype "passive"))
      (node (ref "D5") (pin "2") (pinfunction "K_2") (pintype "passive"))
      (node (ref "U1") (pin "32") (pinfunction "VB1_32") (pintype "passive"))
    )
    (net (code "42") (name "Net-(D6-K)") (class "Default")
      (node (ref "C13") (pin "1") (pinfunction "1_1") (pintype "passive"))
      (node (ref "D6") (pin "2") (pinfunction "K_2") (pintype "passive"))
      (node (ref "U1") (pin "29") (pinfunction "VB2_29") (pintype "passive"))
    )
    (net (code "43") (name "Net-(D7-K)") (class "Default")
      (node (ref "C14") (pin "1") (pinfunction "1_1") (pintype "passive"))
      (node (ref "D7") (pin "2") (pinfunction "K_2") (pintype "passive"))
      (node (ref "U1") (pin "26") (pinfunction "VB3_26") (pintype "passive"))
    )
    (net (code "44") (name "Net-(DEBUG1-CLK)") (class "Default")
      (node (ref "DEBUG1") (pin "3") (pinfunction "CLK_3") (pintype "passive"))
      (node (ref "R18") (pin "1") (pinfunction "1_1") (pintype "passive"))
    )
    (net (code "45") (name "Net-(DEBUG1-DIO)") (class "Default")
      (node (ref "DEBUG1") (pin "4") (pinfunction "DIO_4") (pintype "passive"))
      (node (ref "R21") (pin "1") (pinfunction "1_1") (pintype "passive"))
    )
    (net (code "46") (name "Net-(DZ1-K)") (class "Default")
      (node (ref "DZ1") (pin "2") (pinfunction "K_2") (pintype "passive"))
      (node (ref "Q2") (pin "1") (pinfunction "G_1") (pintype "passive"))
      (node (ref "R1") (pin "2") (pinfunction "2_2") (pintype "passive"))
      (node (ref "R2") (pin "1") (pinfunction "1_1") (pintype "passive"))
    )
    (net (code "47") (name "Net-(IC1-CS)") (class "Default")
      (node (ref "IC1") (pin "4") (pinfunction "CS_4") (pintype "passive"))
      (node (ref "R4") (pin "1") (pinfunction "1_1") (pintype "passive"))
      (node (ref "R5") (pin "1") (pinfunction "1_1") (pintype "passive"))
    )
    (net (code "48") (name "Net-(IC1-FB)") (class "Default")
      (node (ref "IC1") (pin "3") (pinfunction "FB_3") (pintype "passive"))
      (node (ref "R10") (pin "1") (pinfunction "1_1") (pintype "passive"))
      (node (ref "R7") (pin "1") (pinfunction "1_1") (pintype "passive"))
    )
    (net (code "49") (name "Net-(IC1-VDD)") (class "Default")
      (node (ref "C8") (pin "2") (pinfunction "2_2") (pintype "passive"))
      (node (ref "IC1") (pin "1") (pinfunction "VDD_1") (pintype "passive"))
      (node (ref "R11") (pin "2") (pinfunction "2_2") (pintype "passive"))
    )
    (net (code "50") (name "Net-(JP1-Pad2)") (class "Default")
      (node (ref "JP1") (pin "2") (pinfunction "2_2") (pintype "passive"))
      (node (ref "R14") (pin "1") (pinfunction "1_1") (pintype "passive"))
    )
    (net (code "51") (name "Net-(JP1-Pad3)") (class "Default")
      (node (ref "JP1") (pin "3") (pinfunction "3_3") (pintype "passive"))
      (node (ref "R17") (pin "1") (pinfunction "1_1") (pintype "passive"))
    )
    (net (code "52") (name "Net-(Q1-B)") (class "Default")
      (node (ref "Q1") (pin "1") (pinfunction "B_1") (pintype "passive"))
      (node (ref "R6") (pin "2") (pinfunction "2_2") (pintype "passive"))
      (node (ref "R9") (pin "2") (pinfunction "2_2") (pintype "passive"))
    )
    (net (code "53") (name "Net-(Q3-G)") (class "Default")
      (node (ref "Q3") (pin "1") (pinfunction "G_1") (pintype "passive"))
      (node (ref "R23") (pin "2") (pinfunction "2_2") (pintype "passive"))
      (node (ref "R26") (pin "2") (pinfunction "2_2") (pintype "passive"))
    )
    (net (code "54") (name "Net-(Q4-G)") (class "Default")
      (node (ref "Q4") (pin "1") (pinfunction "G_1") (pintype "passive"))
      (node (ref "R24") (pin "2") (pinfunction "2_2") (pintype "passive"))
      (node (ref "R27") (pin "2") (pinfunction "2_2") (pintype "passive"))
    )
    (net (code "55") (name "Net-(Q5-G)") (class "Default")
      (node (ref "Q5") (pin "1") (pinfunction "G_1") (pintype "passive"))
      (node (ref "R25") (pin "2") (pinfunction "2_2") (pintype "passive"))
      (node (ref "R28") (pin "2") (pinfunction "2_2") (pintype "passive"))
    )
    (net (code "56") (name "Net-(Q6-G)") (class "Default")
      (node (ref "Q6") (pin "1") (pinfunction "G_1") (pintype "passive"))
      (node (ref "R30") (pin "2") (pinfunction "2_2") (pintype "passive"))
      (node (ref "R33") (pin "2") (pinfunction "2_2") (pintype "passive"))
    )
    (net (code "57") (name "Net-(Q7-G)") (class "Default")
      (node (ref "Q7") (pin "1") (pinfunction "G_1") (pintype "passive"))
      (node (ref "R31") (pin "2") (pinfunction "2_2") (pintype "passive"))
      (node (ref "R34") (pin "2") (pinfunction "2_2") (pintype "passive"))
    )
    (net (code "58") (name "Net-(Q8-G)") (class "Default")
      (node (ref "Q8") (pin "1") (pinfunction "G_1") (pintype "passive"))
      (node (ref "R32") (pin "2") (pinfunction "2_2") (pintype "passive"))
      (node (ref "R35") (pin "2") (pinfunction "2_2") (pintype "passive"))
    )
    (net (code "59") (name "Net-(R13-Pad1)") (class "Default")
      (node (ref "R13") (pin "1") (pinfunction "1_1") (pintype "passive"))
      (node (ref "R15") (pin "2") (pinfunction "2_2") (pintype "passive"))
      (node (ref "RT1") (pin "2") (pinfunction "2_2") (pintype "passive"))
    )
    (net (code "60") (name "Net-(U1-PA7{slash}OP1P1)") (class "Default")
      (node (ref "R42") (pin "2") (pinfunction "2_2") (pintype "passive"))
      (node (ref "U1") (pin "13") (pinfunction "PA7/OP1P1_13") (pintype "passive"))
    )
    (net (code "61") (name "Net-(U1-PB1{slash}AD9)") (class "Default")
      (node (ref "C26") (pin "1") (pinfunction "1_1") (pintype "passive"))
      (node (ref "R42") (pin "1") (pinfunction "1_1") (pintype "passive"))
      (node (ref "U1") (pin "15") (pinfunction "PB1/AD9_15") (pintype "passive"))
    )
  )
)
